# USB_Experiment_Board.net
KiCad netlist of a schematic drawn in EAGLE
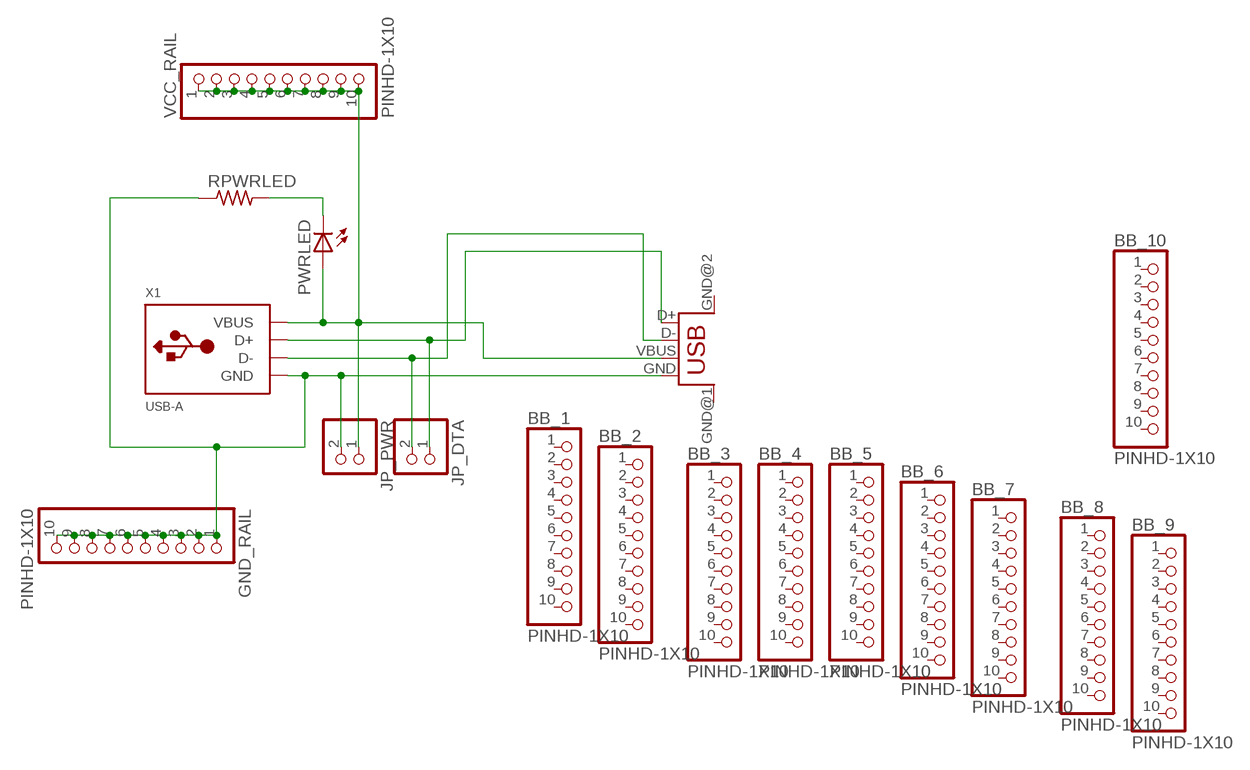
[diagram p0: schematic, sheet 1]

(export (version "E")
  (design (tool "Eeschema 10.0.6"))
  (components
    (comp (ref "BB_1")
      (value "PINHD-1X10")
      (footprint "eagle-import:1X10-BIG")
      (libsource (lib "eagle-import") (part "PINHD-1X10"))
    )
    (comp (ref "BB_2")
      (value "PINHD-1X10")
      (footprint "eagle-import:1X10-BIG")
      (libsource (lib "eagle-import") (part "PINHD-1X10"))
    )
    (comp (ref "BB_3")
      (value "PINHD-1X10")
      (footprint "eagle-import:1X10-BIG")
      (libsource (lib "eagle-import") (part "PINHD-1X10"))
    )
    (comp (ref "BB_4")
      (value "PINHD-1X10")
      (footprint "eagle-import:1X10-BIG")
      (libsource (lib "eagle-import") (part "PINHD-1X10"))
    )
    (comp (ref "BB_5")
      (value "PINHD-1X10")
      (footprint "eagle-import:1X10-BIG")
      (libsource (lib "eagle-import") (part "PINHD-1X10"))
    )
    (comp (ref "BB_6")
      (value "PINHD-1X10")
      (footprint "eagle-import:1X10-BIG")
      (libsource (lib "eagle-import") (part "PINHD-1X10"))
    )
    (comp (ref "BB_7")
      (value "PINHD-1X10")
      (footprint "eagle-import:1X10-BIG")
      (libsource (lib "eagle-import") (part "PINHD-1X10"))
    )
    (comp (ref "BB_8")
      (value "PINHD-1X10")
      (footprint "eagle-import:1X10-BIG")
      (libsource (lib "eagle-import") (part "PINHD-1X10"))
    )
    (comp (ref "BB_9")
      (value "PINHD-1X10")
      (footprint "eagle-import:1X10-BIG")
      (libsource (lib "eagle-import") (part "PINHD-1X10"))
    )
    (comp (ref "BB_10")
      (value "PINHD-1X10")
      (footprint "eagle-import:1X10-BIG")
      (libsource (lib "eagle-import") (part "PINHD-1X10"))
    )
    (comp (ref "GND_RAIL")
      (value "PINHD-1X10")
      (footprint "eagle-import:1X10-BIG")
      (libsource (lib "eagle-import") (part "PINHD-1X10"))
    )
    (comp (ref "JP_DTA")
      (value "PINHD-1X2")
      (footprint "eagle-import:1X02")
      (libsource (lib "eagle-import") (part "PINHD-1X2"))
    )
    (comp (ref "JP_PWR")
      (value "PINHD-1X2")
      (footprint "eagle-import:1X02")
      (libsource (lib "eagle-import") (part "PINHD-1X2"))
    )
    (comp (ref "PWRLED")
      (value "LEDCHIPLED_0805")
      (footprint "eagle-import:CHIPLED_0805")
      (libsource (lib "eagle-import") (part "LEDCHIPLED_0805"))
    )
    (comp (ref "RPWRLED")
      (value "R-US_R0805")
      (footprint "eagle-import:R0805")
      (libsource (lib "eagle-import") (part "R-US_R0805"))
    )
    (comp (ref "U$1")
      (value "USB")
      (footprint "eagle-import:USB-FEMALE-A-PTH")
      (libsource (lib "eagle-import") (part "USB"))
    )
    (comp (ref "VCC_RAIL")
      (value "PINHD-1X10")
      (footprint "eagle-import:1X10-BIG")
      (libsource (lib "eagle-import") (part "PINHD-1X10"))
    )
    (comp (ref "X1")
      (value "USB-A")
      (footprint "eagle-import:MOLEX_480371000")
      (libsource (lib "eagle-import") (part "USB-A"))
    )
  )
  (nets
    (net (code "1") (name "Net-(PWRLED-PadC)") (class "Default")
      (node (ref "PWRLED") (pin "C") (pinfunction "C_C") (pintype "passive"))
      (node (ref "RPWRLED") (pin "2") (pinfunction "2_2") (pintype "passive"))
    )
    (net (code "2") (name "Net-(X1-D+)") (class "Default")
      (node (ref "JP_DTA") (pin "1") (pinfunction "1_1") (pintype "passive"))
      (node (ref "U$1") (pin "D+") (pinfunction "D+_D+") (pintype "bidirectional"))
      (node (ref "X1") (pin "3") (pinfunction "D+_3") (pintype "bidirectional"))
    )
    (net (code "3") (name "Net-(X1-D-)") (class "Default")
      (node (ref "JP_DTA") (pin "2") (pinfunction "2_2") (pintype "passive"))
      (node (ref "U$1") (pin "D-") (pinfunction "D-_D-") (pintype "bidirectional"))
      (node (ref "X1") (pin "2") (pinfunction "D-_2") (pintype "bidirectional"))
    )
    (net (code "4") (name "Net-(X1-GND)") (class "Default")
      (node (ref "GND_RAIL") (pin "1") (pinfunction "1_1") (pintype "passive"))
      (node (ref "GND_RAIL") (pin "10") (pinfunction "10_10") (pintype "passive"))
      (node (ref "GND_RAIL") (pin "2") (pinfunction "2_2") (pintype "passive"))
      (node (ref "GND_RAIL") (pin "3") (pinfunction "3_3") (pintype "passive"))
      (node (ref "GND_RAIL") (pin "4") (pinfunction "4_4") (pintype "passive"))
      (node (ref "GND_RAIL") (pin "5") (pinfunction "5_5") (pintype "passive"))
      (node (ref "GND_RAIL") (pin "6") (pinfunction "6_6") (pintype "passive"))
      (node (ref "GND_RAIL") (pin "7") (pinfunction "7_7") (pintype "passive"))
      (node (ref "GND_RAIL") (pin "8") (pinfunction "8_8") (pintype "passive"))
      (node (ref "GND_RAIL") (pin "9") (pinfunction "9_9") (pintype "passive"))
      (node (ref "JP_PWR") (pin "2") (pinfunction "2_2") (pintype "passive"))
      (node (ref "RPWRLED") (pin "1") (pinfunction "1_1") (pintype "passive"))
      (node (ref "U$1") (pin "GND") (pinfunction "GND_GND") (pintype "bidirectional"))
      (node (ref "X1") (pin "4") (pinfunction "GND_4") (pintype "power_in"))
    )
    (net (code "5") (name "Net-(X1-VBUS)") (class "Default")
      (node (ref "JP_PWR") (pin "1") (pinfunction "1_1") (pintype "passive"))
      (node (ref "PWRLED") (pin "A") (pinfunction "A_A") (pintype "passive"))
      (node (ref "U$1") (pin "VBUS") (pinfunction "VBUS_VBUS") (pintype "bidirectional"))
      (node (ref "VCC_RAIL") (pin "1") (pinfunction "1_1") (pintype "passive"))
      (node (ref "VCC_RAIL") (pin "10") (pinfunction "10_10") (pintype "passive"))
      (node (ref "VCC_RAIL") (pin "2") (pinfunction "2_2") (pintype "passive"))
      (node (ref "VCC_RAIL") (pin "3") (pinfunction "3_3") (pintype "passive"))
      (node (ref "VCC_RAIL") (pin "4") (pinfunction "4_4") (pintype "passive"))
      (node (ref "VCC_RAIL") (pin "5") (pinfunction "5_5") (pintype "passive"))
      (node (ref "VCC_RAIL") (pin "6") (pinfunction "6_6") (pintype "passive"))
      (node (ref "VCC_RAIL") (pin "7") (pinfunction "7_7") (pintype "passive"))
      (node (ref "VCC_RAIL") (pin "8") (pinfunction "8_8") (pintype "passive"))
      (node (ref "VCC_RAIL") (pin "9") (pinfunction "9_9") (pintype "passive"))
      (node (ref "X1") (pin "1") (pinfunction "VBUS_1") (pintype "power_in"))
    )
    (net (code "6") (name "unconnected-(BB_1-Pad1)") (class "Default")
      (node (ref "BB_1") (pin "1") (pinfunction "1_1") (pintype "passive"))
    )
    (net (code "7") (name "unconnected-(BB_1-Pad2)") (class "Default")
      (node (ref "BB_1") (pin "2") (pinfunction "2_2") (pintype "passive"))
    )
    (net (code "8") (name "unconnected-(BB_1-Pad3)") (class "Default")
      (node (ref "BB_1") (pin "3") (pinfunction "3_3") (pintype "passive"))
    )
    (net (code "9") (name "unconnected-(BB_1-Pad4)") (class "Default")
      (node (ref "BB_1") (pin "4") (pinfunction "4_4") (pintype "passive"))
    )
    (net (code "10") (name "unconnected-(BB_1-Pad5)") (class "Default")
      (node (ref "BB_1") (pin "5") (pinfunction "5_5") (pintype "passive"))
    )
    (net (code "11") (name "unconnected-(BB_1-Pad6)") (class "Default")
      (node (ref "BB_1") (pin "6") (pinfunction "6_6") (pintype "passive"))
    )
    (net (code "12") (name "unconnected-(BB_1-Pad7)") (class "Default")
      (node (ref "BB_1") (pin "7") (pinfunction "7_7") (pintype "passive"))
    )
    (net (code "13") (name "unconnected-(BB_1-Pad8)") (class "Default")
      (node (ref "BB_1") (pin "8") (pinfunction "8_8") (pintype "passive"))
    )
    (net (code "14") (name "unconnected-(BB_1-Pad9)") (class "Default")
      (node (ref "BB_1") (pin "9") (pinfunction "9_9") (pintype "passive"))
    )
    (net (code "15") (name "unconnected-(BB_1-Pad10)") (class "Default")
      (node (ref "BB_1") (pin "10") (pinfunction "10_10") (pintype "passive"))
    )
    (net (code "16") (name "unconnected-(BB_2-Pad1)") (class "Default")
      (node (ref "BB_2") (pin "1") (pinfunction "1_1") (pintype "passive"))
    )
    (net (code "17") (name "unconnected-(BB_2-Pad2)") (class "Default")
      (node (ref "BB_2") (pin "2") (pinfunction "2_2") (pintype "passive"))
    )
    (net (code "18") (name "unconnected-(BB_2-Pad3)") (class "Default")
      (node (ref "BB_2") (pin "3") (pinfunction "3_3") (pintype "passive"))
    )
    (net (code "19") (name "unconnected-(BB_2-Pad4)") (class "Default")
      (node (ref "BB_2") (pin "4") (pinfunction "4_4") (pintype "passive"))
    )
    (net (code "20") (name "unconnected-(BB_2-Pad5)") (class "Default")
      (node (ref "BB_2") (pin "5") (pinfunction "5_5") (pintype "passive"))
    )
    (net (code "21") (name "unconnected-(BB_2-Pad6)") (class "Default")
      (node (ref "BB_2") (pin "6") (pinfunction "6_6") (pintype "passive"))
    )
    (net (code "22") (name "unconnected-(BB_2-Pad7)") (class "Default")
      (node (ref "BB_2") (pin "7") (pinfunction "7_7") (pintype "passive"))
    )
    (net (code "23") (name "unconnected-(BB_2-Pad8)") (class "Default")
      (node (ref "BB_2") (pin "8") (pinfunction "8_8") (pintype "passive"))
    )
    (net (code "24") (name "unconnected-(BB_2-Pad9)") (class "Default")
      (node (ref "BB_2") (pin "9") (pinfunction "9_9") (pintype "passive"))
    )
    (net (code "25") (name "unconnected-(BB_2-Pad10)") (class "Default")
      (node (ref "BB_2") (pin "10") (pinfunction "10_10") (pintype "passive"))
    )
    (net (code "26") (name "unconnected-(BB_3-Pad1)") (class "Default")
      (node (ref "BB_3") (pin "1") (pinfunction "1_1") (pintype "passive"))
    )
    (net (code "27") (name "unconnected-(BB_3-Pad2)") (class "Default")
      (node (ref "BB_3") (pin "2") (pinfunction "2_2") (pintype "passive"))
    )
    (net (code "28") (name "unconnected-(BB_3-Pad3)") (class "Default")
      (node (ref "BB_3") (pin "3") (pinfunction "3_3") (pintype "passive"))
    )
    (net (code "29") (name "unconnected-(BB_3-Pad4)") (class "Default")
      (node (ref "BB_3") (pin "4") (pinfunction "4_4") (pintype "passive"))
    )
    (net (code "30") (name "unconnected-(BB_3-Pad5)") (class "Default")
      (node (ref "BB_3") (pin "5") (pinfunction "5_5") (pintype "passive"))
    )
    (net (code "31") (name "unconnected-(BB_3-Pad6)") (class "Default")
      (node (ref "BB_3") (pin "6") (pinfunction "6_6") (pintype "passive"))
    )
    (net (code "32") (name "unconnected-(BB_3-Pad7)") (class "Default")
      (node (ref "BB_3") (pin "7") (pinfunction "7_7") (pintype "passive"))
    )
    (net (code "33") (name "unconnected-(BB_3-Pad8)") (class "Default")
      (node (ref "BB_3") (pin "8") (pinfunction "8_8") (pintype "passive"))
    )
    (net (code "34") (name "unconnected-(BB_3-Pad9)") (class "Default")
      (node (ref "BB_3") (pin "9") (pinfunction "9_9") (pintype "passive"))
    )
    (net (code "35") (name "unconnected-(BB_3-Pad10)") (class "Default")
      (node (ref "BB_3") (pin "10") (pinfunction "10_10") (pintype "passive"))
    )
    (net (code "36") (name "unconnected-(BB_4-Pad1)") (class "Default")
      (node (ref "BB_4") (pin "1") (pinfunction "1_1") (pintype "passive"))
    )
    (net (code "37") (name "unconnected-(BB_4-Pad2)") (class "Default")
      (node (ref "BB_4") (pin "2") (pinfunction "2_2") (pintype "passive"))
    )
    (net (code "38") (name "unconnected-(BB_4-Pad3)") (class "Default")
      (node (ref "BB_4") (pin "3") (pinfunction "3_3") (pintype "passive"))
    )
    (net (code "39") (name "unconnected-(BB_4-Pad4)") (class "Default")
      (node (ref "BB_4") (pin "4") (pinfunction "4_4") (pintype "passive"))
    )
    (net (code "40") (name "unconnected-(BB_4-Pad5)") (class "Default")
      (node (ref "BB_4") (pin "5") (pinfunction "5_5") (pintype "passive"))
    )
    (net (code "41") (name "unconnected-(BB_4-Pad6)") (class "Default")
      (node (ref "BB_4") (pin "6") (pinfunction "6_6") (pintype "passive"))
    )
    (net (code "42") (name "unconnected-(BB_4-Pad7)") (class "Default")
      (node (ref "BB_4") (pin "7") (pinfunction "7_7") (pintype "passive"))
    )
    (net (code "43") (name "unconnected-(BB_4-Pad8)") (class "Default")
      (node (ref "BB_4") (pin "8") (pinfunction "8_8") (pintype "passive"))
    )
    (net (code "44") (name "unconnected-(BB_4-Pad9)") (class "Default")
      (node (ref "BB_4") (pin "9") (pinfunction "9_9") (pintype "passive"))
    )
    (net (code "45") (name "unconnected-(BB_4-Pad10)") (class "Default")
      (node (ref "BB_4") (pin "10") (pinfunction "10_10") (pintype "passive"))
    )
    (net (code "46") (name "unconnected-(BB_5-Pad1)") (class "Default")
      (node (ref "BB_5") (pin "1") (pinfunction "1_1") (pintype "passive"))
    )
    (net (code "47") (name "unconnected-(BB_5-Pad2)") (class "Default")
      (node (ref "BB_5") (pin "2") (pinfunction "2_2") (pintype "passive"))
    )
    (net (code "48") (name "unconnected-(BB_5-Pad3)") (class "Default")
      (node (ref "BB_5") (pin "3") (pinfunction "3_3") (pintype "passive"))
    )
    (net (code "49") (name "unconnected-(BB_5-Pad4)") (class "Default")
      (node (ref "BB_5") (pin "4") (pinfunction "4_4") (pintype "passive"))
    )
    (net (code "50") (name "unconnected-(BB_5-Pad5)") (class "Default")
      (node (ref "BB_5") (pin "5") (pinfunction "5_5") (pintype "passive"))
    )
    (net (code "51") (name "unconnected-(BB_5-Pad6)") (class "Default")
      (node (ref "BB_5") (pin "6") (pinfunction "6_6") (pintype "passive"))
    )
    (net (code "52") (name "unconnected-(BB_5-Pad7)") (class "Default")
      (node (ref "BB_5") (pin "7") (pinfunction "7_7") (pintype "passive"))
    )
    (net (code "53") (name "unconnected-(BB_5-Pad8)") (class "Default")
      (node (ref "BB_5") (pin "8") (pinfunction "8_8") (pintype "passive"))
    )
    (net (code "54") (name "unconnected-(BB_5-Pad9)") (class "Default")
      (node (ref "BB_5") (pin "9") (pinfunction "9_9") (pintype "passive"))
    )
    (net (code "55") (name "unconnected-(BB_5-Pad10)") (class "Default")
      (node (ref "BB_5") (pin "10") (pinfunction "10_10") (pintype "passive"))
    )
    (net (code "56") (name "unconnected-(BB_6-Pad1)") (class "Default")
      (node (ref "BB_6") (pin "1") (pinfunction "1_1") (pintype "passive"))
    )
    (net (code "57") (name "unconnected-(BB_6-Pad2)") (class "Default")
      (node (ref "BB_6") (pin "2") (pinfunction "2_2") (pintype "passive"))
    )
    (net (code "58") (name "unconnected-(BB_6-Pad3)") (class "Default")
      (node (ref "BB_6") (pin "3") (pinfunction "3_3") (pintype "passive"))
    )
    (net (code "59") (name "unconnected-(BB_6-Pad4)") (class "Default")
      (node (ref "BB_6") (pin "4") (pinfunction "4_4") (pintype "passive"))
    )
    (net (code "60") (name "unconnected-(BB_6-Pad5)") (class "Default")
      (node (ref "BB_6") (pin "5") (pinfunction "5_5") (pintype "passive"))
    )
    (net (code "61") (name "unconnected-(BB_6-Pad6)") (class "Default")
      (node (ref "BB_6") (pin "6") (pinfunction "6_6") (pintype "passive"))
    )
    (net (code "62") (name "unconnected-(BB_6-Pad7)") (class "Default")
      (node (ref "BB_6") (pin "7") (pinfunction "7_7") (pintype "passive"))
    )
    (net (code "63") (name "unconnected-(BB_6-Pad8)") (class "Default")
      (node (ref "BB_6") (pin "8") (pinfunction "8_8") (pintype "passive"))
    )
    (net (code "64") (name "unconnected-(BB_6-Pad9)") (class "Default")
      (node (ref "BB_6") (pin "9") (pinfunction "9_9") (pintype "passive"))
    )
    (net (code "65") (name "unconnected-(BB_6-Pad10)") (class "Default")
      (node (ref "BB_6") (pin "10") (pinfunction "10_10") (pintype "passive"))
    )
    (net (code "66") (name "unconnected-(BB_7-Pad1)") (class "Default")
      (node (ref "BB_7") (pin "1") (pinfunction "1_1") (pintype "passive"))
    )
    (net (code "67") (name "unconnected-(BB_7-Pad2)") (class "Default")
      (node (ref "BB_7") (pin "2") (pinfunction "2_2") (pintype "passive"))
    )
    (net (code "68") (name "unconnected-(BB_7-Pad3)") (class "Default")
      (node (ref "BB_7") (pin "3") (pinfunction "3_3") (pintype "passive"))
    )
    (net (code "69") (name "unconnected-(BB_7-Pad4)") (class "Default")
      (node (ref "BB_7") (pin "4") (pinfunction "4_4") (pintype "passive"))
    )
    (net (code "70") (name "unconnected-(BB_7-Pad5)") (class "Default")
      (node (ref "BB_7") (pin "5") (pinfunction "5_5") (pintype "passive"))
    )
    (net (code "71") (name "unconnected-(BB_7-Pad6)") (class "Default")
      (node (ref "BB_7") (pin "6") (pinfunction "6_6") (pintype "passive"))
    )
    (net (code "72") (name "unconnected-(BB_7-Pad7)") (class "Default")
      (node (ref "BB_7") (pin "7") (pinfunction "7_7") (pintype "passive"))
    )
    (net (code "73") (name "unconnected-(BB_7-Pad8)") (class "Default")
      (node (ref "BB_7") (pin "8") (pinfunction "8_8") (pintype "passive"))
    )
    (net (code "74") (name "unconnected-(BB_7-Pad9)") (class "Default")
      (node (ref "BB_7") (pin "9") (pinfunction "9_9") (pintype "passive"))
    )
    (net (code "75") (name "unconnected-(BB_7-Pad10)") (class "Default")
      (node (ref "BB_7") (pin "10") (pinfunction "10_10") (pintype "passive"))
    )
    (net (code "76") (name "unconnected-(BB_8-Pad1)") (class "Default")
      (node (ref "BB_8") (pin "1") (pinfunction "1_1") (pintype "passive"))
    )
    (net (code "77") (name "unconnected-(BB_8-Pad2)") (class "Default")
      (node (ref "BB_8") (pin "2") (pinfunction "2_2") (pintype "passive"))
    )
    (net (code "78") (name "unconnected-(BB_8-Pad3)") (class "Default")
      (node (ref "BB_8") (pin "3") (pinfunction "3_3") (pintype "passive"))
    )
    (net (code "79") (name "unconnected-(BB_8-Pad4)") (class "Default")
      (node (ref "BB_8") (pin "4") (pinfunction "4_4") (pintype "passive"))
    )
    (net (code "80") (name "unconnected-(BB_8-Pad5)") (class "Default")
      (node (ref "BB_8") (pin "5") (pinfunction "5_5") (pintype "passive"))
    )
    (net (code "81") (name "unconnected-(BB_8-Pad6)") (class "Default")
      (node (ref "BB_8") (pin "6") (pinfunction "6_6") (pintype "passive"))
    )
    (net (code "82") (name "unconnected-(BB_8-Pad7)") (class "Default")
      (node (ref "BB_8") (pin "7") (pinfunction "7_7") (pintype "passive"))
    )
    (net (code "83") (name "unconnected-(BB_8-Pad8)") (class "Default")
      (node (ref "BB_8") (pin "8") (pinfunction "8_8") (pintype "passive"))
    )
    (net (code "84") (name "unconnected-(BB_8-Pad9)") (class "Default")
      (node (ref "BB_8") (pin "9") (pinfunction "9_9") (pintype "passive"))
    )
    (net (code "85") (name "unconnected-(BB_8-Pad10)") (class "Default")
      (node (ref "BB_8") (pin "10") (pinfunction "10_10") (pintype "passive"))
    )
    (net (code "86") (name "unconnected-(BB_9-Pad1)") (class "Default")
      (node (ref "BB_9") (pin "1") (pinfunction "1_1") (pintype "passive"))
    )
    (net (code "87") (name "unconnected-(BB_9-Pad2)") (class "Default")
      (node (ref "BB_9") (pin "2") (pinfunction "2_2") (pintype "passive"))
    )
    (net (code "88") (name "unconnected-(BB_9-Pad3)") (class "Default")
      (node (ref "BB_9") (pin "3") (pinfunction "3_3") (pintype "passive"))
    )
    (net (code "89") (name "unconnected-(BB_9-Pad4)") (class "Default")
      (node (ref "BB_9") (pin "4") (pinfunction "4_4") (pintype "passive"))
    )
    (net (code "90") (name "unconnected-(BB_9-Pad5)") (class "Default")
      (node (ref "BB_9") (pin "5") (pinfunction "5_5") (pintype "passive"))
    )
    (net (code "91") (name "unconnected-(BB_9-Pad6)") (class "Default")
      (node (ref "BB_9") (pin "6") (pinfunction "6_6") (pintype "passive"))
    )
    (net (code "92") (name "unconnected-(BB_9-Pad7)") (class "Default")
      (node (ref "BB_9") (pin "7") (pinfunction "7_7") (pintype "passive"))
    )
    (net (code "93") (name "unconnected-(BB_9-Pad8)") (class "Default")
      (node (ref "BB_9") (pin "8") (pinfunction "8_8") (pintype "passive"))
    )
    (net (code "94") (name "unconnected-(BB_9-Pad9)") (class "Default")
      (node (ref "BB_9") (pin "9") (pinfunction "9_9") (pintype "passive"))
    )
    (net (code "95") (name "unconnected-(BB_9-Pad10)") (class "Default")
      (node (ref "BB_9") (pin "10") (pinfunction "10_10") (pintype "passive"))
    )
    (net (code "96") (name "unconnected-(BB_10-Pad1)") (class "Default")
      (node (ref "BB_10") (pin "1") (pinfunction "1_1") (pintype "passive"))
    )
    (net (code "97") (name "unconnected-(BB_10-Pad2)") (class "Default")
      (node (ref "BB_10") (pin "2") (pinfunction "2_2") (pintype "passive"))
    )
    (net (code "98") (name "unconnected-(BB_10-Pad3)") (class "Default")
      (node (ref "BB_10") (pin "3") (pinfunction "3_3") (pintype "passive"))
    )
    (net (code "99") (name "unconnected-(BB_10-Pad4)") (class "Default")
      (node (ref "BB_10") (pin "4") (pinfunction "4_4") (pintype "passive"))
    )
    (net (code "100") (name "unconnected-(BB_10-Pad5)") (class "Default")
      (node (ref "BB_10") (pin "5") (pinfunction "5_5") (pintype "passive"))
    )
    (net (code "101") (name "unconnected-(BB_10-Pad6)") (class "Default")
      (node (ref "BB_10") (pin "6") (pinfunction "6_6") (pintype "passive"))
    )
    (net (code "102") (name "unconnected-(BB_10-Pad7)") (class "Default")
      (node (ref "BB_10") (pin "7") (pinfunction "7_7") (pintype "passive"))
    )
    (net (code "103") (name "unconnected-(BB_10-Pad8)") (class "Default")
      (node (ref "BB_10") (pin "8") (pinfunction "8_8") (pintype "passive"))
    )
    (net (code "104") (name "unconnected-(BB_10-Pad9)") (class "Default")
      (node (ref "BB_10") (pin "9") (pinfunction "9_9") (pintype "passive"))
    )
    (net (code "105") (name "unconnected-(BB_10-Pad10)") (class "Default")
      (node (ref "BB_10") (pin "10") (pinfunction "10_10") (pintype "passive"))
    )
    (net (code "106") (name "unconnected-(U$1-GND-PadGND@1)") (class "Default")
      (node (ref "U$1") (pin "GND@1") (pinfunction "GND_GND@1") (pintype "bidirectional"))
    )
    (net (code "107") (name "unconnected-(U$1-GND-PadGND@2)") (class "Default")
      (node (ref "U$1") (pin "GND@2") (pinfunction "GND_GND@2") (pintype "bidirectional"))
    )
  )
)
